# Channel_3.net
KiCad netlist of a schematic drawn in Altium Designer
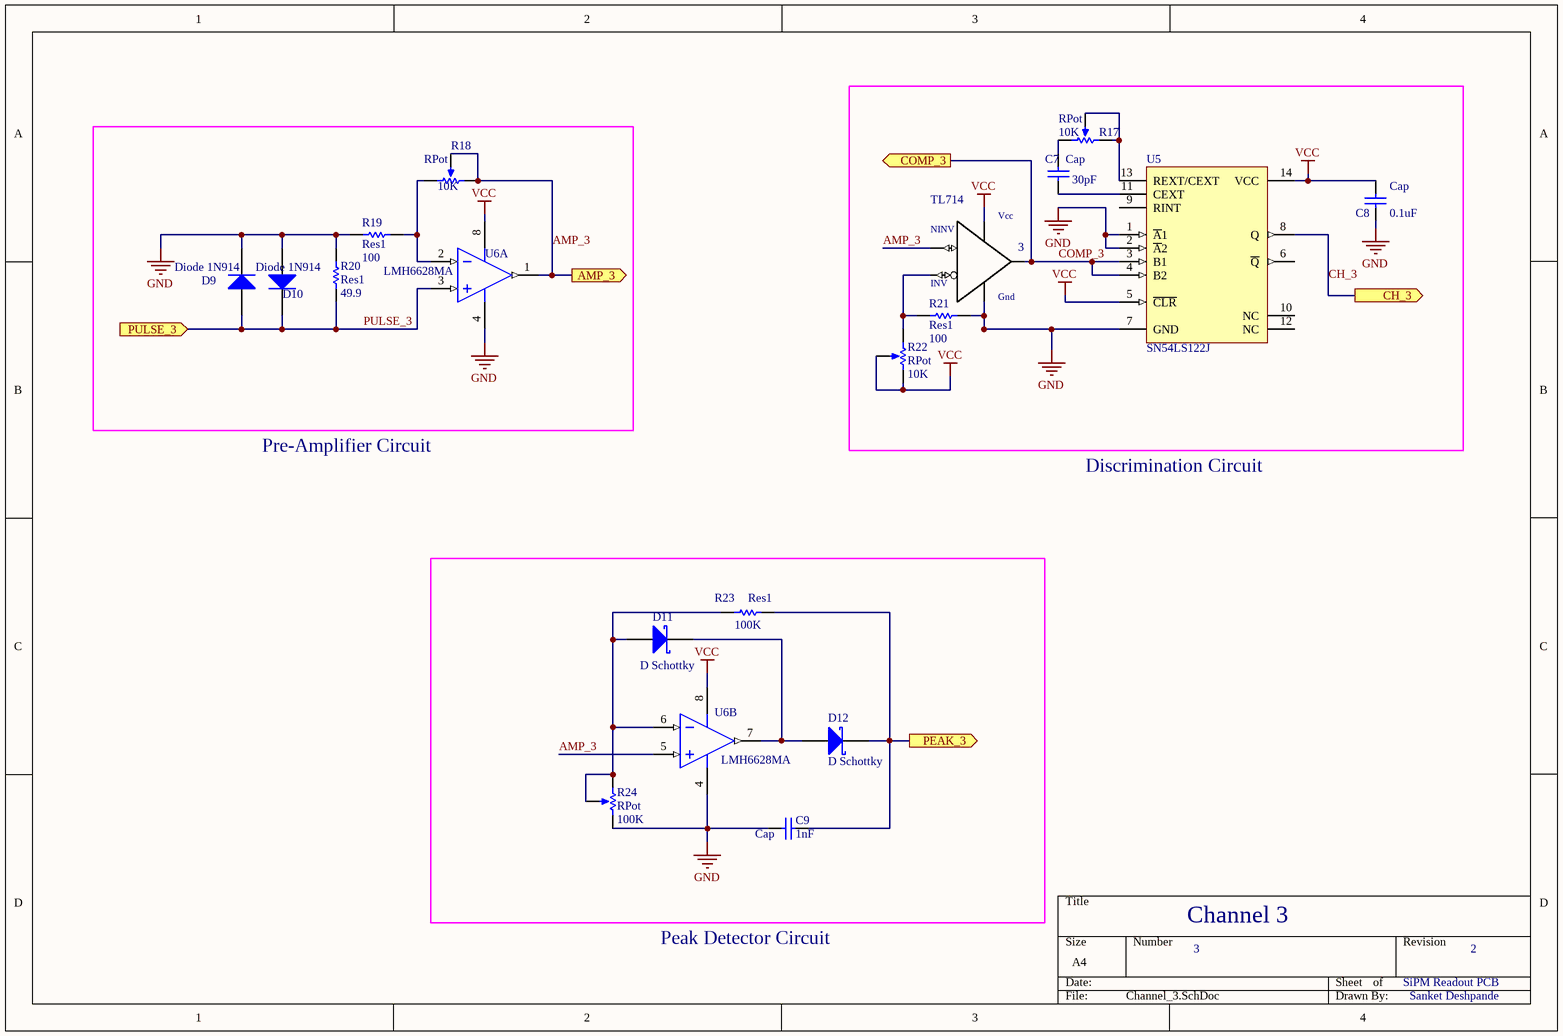
[diagram p0: Channel_3.SchDoc]

(export (version "E")
  (design (tool "Eeschema 10.0.6"))
  (components
    (comp (ref "3")
      (value "TL714")
      (footprint "SO-08M")
      (fields (field (name "MF") "Texas Instruments"))
      (libsource (lib "TL714") (part "TL714"))
    )
    (comp (ref "C7")
      (value "Cap")
      (footprint "RAD-0.3")
      (description "Capacitor")
      (fields (field (name "ALTIUM_VALUE") "30pF") (field (name "PUBLISHER") "Altium Limited"))
      (libsource (lib "Miscellaneous Devices") (part "Cap"))
    )
    (comp (ref "C8")
      (value "Cap")
      (footprint "RAD-0.3")
      (description "Capacitor")
      (fields (field (name "ALTIUM_VALUE") "0.1uF") (field (name "PUBLISHER") "Altium Limited"))
      (libsource (lib "Miscellaneous Devices") (part "Cap"))
    )
    (comp (ref "C9")
      (value "Cap")
      (footprint "RAD-0.3")
      (description "Capacitor")
      (fields (field (name "ALTIUM_VALUE") "1nF") (field (name "PUBLISHER") "Altium Limited"))
      (libsource (lib "Miscellaneous Devices") (part "Cap"))
    )
    (comp (ref "D9")
      (value "Diode 1N914")
      (footprint "DO-35")
      (description "High Conductance Fast Diode")
      (fields (field (name "PUBLISHER") "Altium Limited"))
      (libsource (lib "Miscellaneous Devices") (part "Diode 1N914"))
    )
    (comp (ref "D10")
      (value "Diode 1N914")
      (footprint "DO-35")
      (description "High Conductance Fast Diode")
      (fields (field (name "PUBLISHER") "Altium Limited"))
      (libsource (lib "Miscellaneous Devices") (part "Diode 1N914"))
    )
    (comp (ref "D11")
      (value "D Schottky")
      (footprint "SMB")
      (description "Schottky Diode")
      (fields (field (name "PUBLISHER") "Altium Limited"))
      (libsource (lib "Miscellaneous Devices") (part "D Schottky"))
    )
    (comp (ref "D12")
      (value "D Schottky")
      (footprint "SMB")
      (description "Schottky Diode")
      (fields (field (name "PUBLISHER") "Altium Limited"))
      (libsource (lib "Miscellaneous Devices") (part "D Schottky"))
    )
    (comp (ref "R17")
      (value "RPot")
      (footprint "VR5")
      (description "Potentiometer")
      (fields (field (name "ALTIUM_VALUE") "10K") (field (name "PUBLISHER") "Altium Limited"))
      (libsource (lib "Miscellaneous Devices") (part "RPot"))
    )
    (comp (ref "R18")
      (value "RPot")
      (footprint "VR5")
      (description "Potentiometer")
      (fields (field (name "ALTIUM_VALUE") "10K") (field (name "PUBLISHER") "Altium Limited"))
      (libsource (lib "Miscellaneous Devices") (part "RPot"))
    )
    (comp (ref "R19")
      (value "Res1")
      (footprint "AXIAL-0.3")
      (description "Resistor")
      (fields (field (name "ALTIUM_VALUE") "100") (field (name "PUBLISHER") "Altium Limited"))
      (libsource (lib "Miscellaneous Devices") (part "Res1"))
    )
    (comp (ref "R20")
      (value "Res1")
      (footprint "AXIAL-0.3")
      (description "Resistor")
      (fields (field (name "ALTIUM_VALUE") "49.9") (field (name "PUBLISHER") "Altium Limited"))
      (libsource (lib "Miscellaneous Devices") (part "Res1"))
    )
    (comp (ref "R21")
      (value "Res1")
      (footprint "AXIAL-0.3")
      (description "Resistor")
      (fields (field (name "ALTIUM_VALUE") "100") (field (name "PUBLISHER") "Altium Limited"))
      (libsource (lib "Miscellaneous Devices") (part "Res1"))
    )
    (comp (ref "R22")
      (value "RPot")
      (footprint "VR5")
      (description "Potentiometer")
      (fields (field (name "ALTIUM_VALUE") "10K") (field (name "PUBLISHER") "Altium Limited"))
      (libsource (lib "Miscellaneous Devices") (part "RPot"))
    )
    (comp (ref "R23")
      (value "Res1")
      (footprint "AXIAL-0.3")
      (description "Resistor")
      (fields (field (name "ALTIUM_VALUE") "100K") (field (name "PUBLISHER") "Altium Limited"))
      (libsource (lib "Miscellaneous Devices") (part "Res1"))
    )
    (comp (ref "R24")
      (value "RPot")
      (footprint "VR5")
      (description "Potentiometer")
      (fields (field (name "ALTIUM_VALUE") "100K") (field (name "PUBLISHER") "Altium Limited"))
      (libsource (lib "Miscellaneous Devices") (part "RPot"))
    )
    (comp (ref "U5")
      (value "SN54LS122J")
      (footprint "J014")
      (description "Retriggerable Monostable Multivibrator")
      (fields (field (name "PUBLISHER") "Altium Limited"))
      (libsource (lib "TI Logic Multivibrator") (part "SN54LS122J"))
    )
    (comp (ref "U6")
      (value "LMH6628MA")
      (footprint "M08A_N")
      (description "Dual Wideband, Low Noise, Voltage Feedback Op Amp, 8-pin Narrow SOIC")
      (fields (field (name "MANUFACTURER") "National Semiconductor"))
      (libsource (lib "National Semiconductor Amplifier") (part "LMH6628MA"))
    )
  )
  (nets
    (net (code "1") (name "/AMP_3") (class "Default")
      (node (ref "3") (pin "3") (pinfunction "NINV_3") (pintype "bidirectional"))
      (node (ref "R18") (pin "1") (pinfunction "TOP_1") (pintype "passive"))
      (node (ref "R18") (pin "3") (pinfunction "TAP_3") (pintype "passive"))
      (node (ref "U6") (pin "1") (pinfunction "OUT1_1") (pintype "output"))
      (node (ref "U6") (pin "5") (pinfunction "IN2+_5") (pintype "input"))
    )
    (net (code "2") (name "/CH_3") (class "Default")
      (node (ref "U5") (pin "8") (pinfunction "Q_8") (pintype "output"))
    )
    (net (code "3") (name "/COMP_3") (class "Default")
      (node (ref "3") (pin "6") (pinfunction "OUT_6") (pintype "bidirectional"))
      (node (ref "U5") (pin "3") (pinfunction "B1_3") (pintype "input"))
      (node (ref "U5") (pin "4") (pinfunction "B2_4") (pintype "input"))
    )
    (net (code "4") (name "/PEAK_3") (class "Default")
      (node (ref "C9") (pin "2") (pinfunction "2_2") (pintype "passive"))
      (node (ref "D12") (pin "2") (pinfunction "K_2") (pintype "passive"))
      (node (ref "R23") (pin "2") (pinfunction "2_2") (pintype "passive"))
    )
    (net (code "5") (name "/PULSE_3") (class "Default")
      (node (ref "D10") (pin "2") (pinfunction "K_2") (pintype "passive"))
      (node (ref "D9") (pin "1") (pinfunction "A_1") (pintype "passive"))
      (node (ref "R20") (pin "2") (pinfunction "2_2") (pintype "passive"))
      (node (ref "U6") (pin "3") (pinfunction "IN1+_3") (pintype "input"))
    )
    (net (code "6") (name "GND") (class "Default")
      (node (ref "3") (pin "5") (pinfunction "VNEG_5") (pintype "bidirectional"))
      (node (ref "C8") (pin "1") (pinfunction "1_1") (pintype "passive"))
      (node (ref "C9") (pin "1") (pinfunction "1_1") (pintype "passive"))
      (node (ref "D10") (pin "1") (pinfunction "A_1") (pintype "passive"))
      (node (ref "D9") (pin "2") (pinfunction "K_2") (pintype "passive"))
      (node (ref "R19") (pin "1") (pinfunction "1_1") (pintype "passive"))
      (node (ref "R20") (pin "1") (pinfunction "1_1") (pintype "passive"))
      (node (ref "R21") (pin "2") (pinfunction "2_2") (pintype "passive"))
      (node (ref "R24") (pin "2") (pinfunction "BOT_2") (pintype "passive"))
      (node (ref "U5") (pin "1") (pinfunction "~{A}1_1") (pintype "input"))
      (node (ref "U5") (pin "2") (pinfunction "~{A}2_2") (pintype "input"))
      (node (ref "U5") (pin "7") (pinfunction "GND_7") (pintype "power_in"))
      (node (ref "U6") (pin "4") (pinfunction "V-_4") (pintype "power_in"))
    )
    (net (code "7") (name "Net-(3-INV)") (class "Default")
      (node (ref "3") (pin "2") (pinfunction "INV_2") (pintype "bidirectional"))
      (node (ref "R21") (pin "1") (pinfunction "1_1") (pintype "passive"))
      (node (ref "R22") (pin "1") (pinfunction "TOP_1") (pintype "passive"))
    )
    (net (code "8") (name "Net-(D11-A)") (class "Default")
      (node (ref "D11") (pin "1") (pinfunction "A_1") (pintype "passive"))
      (node (ref "R23") (pin "1") (pinfunction "1_1") (pintype "passive"))
      (node (ref "R24") (pin "1") (pinfunction "TOP_1") (pintype "passive"))
      (node (ref "R24") (pin "3") (pinfunction "TAP_3") (pintype "passive"))
      (node (ref "U6") (pin "6") (pinfunction "IN2-_6") (pintype "input"))
    )
    (net (code "9") (name "Net-(D11-K)") (class "Default")
      (node (ref "D11") (pin "2") (pinfunction "K_2") (pintype "passive"))
      (node (ref "D12") (pin "1") (pinfunction "A_1") (pintype "passive"))
      (node (ref "U6") (pin "7") (pinfunction "OUT2_7") (pintype "output"))
    )
    (net (code "10") (name "Net-(R17-BOT)") (class "Default")
      (node (ref "C7") (pin "2") (pinfunction "2_2") (pintype "passive"))
      (node (ref "R17") (pin "2") (pinfunction "BOT_2") (pintype "passive"))
    )
    (net (code "11") (name "Net-(R17-TAP)") (class "Default")
      (node (ref "R17") (pin "1") (pinfunction "TOP_1") (pintype "passive"))
      (node (ref "R17") (pin "3") (pinfunction "TAP_3") (pintype "passive"))
      (node (ref "U5") (pin "13") (pinfunction "REXT/CEXT_13") (pintype "passive"))
    )
    (net (code "12") (name "Net-(R18-BOT)") (class "Default")
      (node (ref "R18") (pin "2") (pinfunction "BOT_2") (pintype "passive"))
      (node (ref "R19") (pin "2") (pinfunction "2_2") (pintype "passive"))
      (node (ref "U6") (pin "2") (pinfunction "IN1-_2") (pintype "input"))
    )
    (net (code "13") (name "Net-(U5-CEXT)") (class "Default")
      (node (ref "C7") (pin "1") (pinfunction "1_1") (pintype "passive"))
      (node (ref "U5") (pin "11") (pinfunction "CEXT_11") (pintype "passive"))
    )
    (net (code "14") (name "VCC") (class "Default")
      (node (ref "3") (pin "8") (pinfunction "VPOS_8") (pintype "bidirectional"))
      (node (ref "C8") (pin "2") (pinfunction "2_2") (pintype "passive"))
      (node (ref "R22") (pin "2") (pinfunction "BOT_2") (pintype "passive"))
      (node (ref "R22") (pin "3") (pinfunction "TAP_3") (pintype "passive"))
      (node (ref "U5") (pin "14") (pinfunction "VCC_14") (pintype "power_in"))
      (node (ref "U5") (pin "5") (pinfunction "~{CLR}_5") (pintype "input"))
      (node (ref "U6") (pin "8") (pinfunction "V+_8") (pintype "power_in"))
    )
    (net (code "15") (name "unconnected-(U5-NC-Pad10)") (class "Default")
      (node (ref "U5") (pin "10") (pinfunction "NC_10") (pintype "passive"))
    )
    (net (code "16") (name "unconnected-(U5-NC-Pad12)") (class "Default")
      (node (ref "U5") (pin "12") (pinfunction "NC_12") (pintype "passive"))
    )
    (net (code "17") (name "unconnected-(U5-RINT-Pad9)") (class "Default")
      (node (ref "U5") (pin "9") (pinfunction "RINT_9") (pintype "passive"))
    )
    (net (code "18") (name "unconnected-(U5-~{Q}-Pad6)") (class "Default")
      (node (ref "U5") (pin "6") (pinfunction "~{Q}_6") (pintype "output"))
    )
  )
)
